# MQ.net
KiCad netlist of a schematic drawn in EAGLE
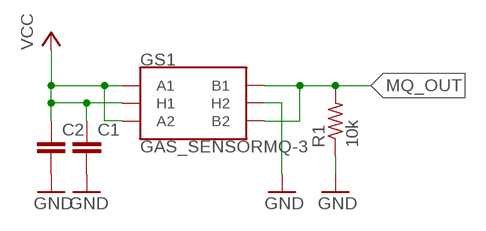
[diagram p0: schematic, sheet 1]

(export (version "E")
  (design (tool "Eeschema 10.0.6"))
  (components
    (comp (ref "C1")
      (value "C-EUC0603")
      (footprint "eagle-import:C0603")
      (libsource (lib "eagle-import") (part "C-EUC0603"))
    )
    (comp (ref "C2")
      (value "C-EUC0603")
      (footprint "eagle-import:C0603")
      (libsource (lib "eagle-import") (part "C-EUC0603"))
    )
    (comp (ref "GS1")
      (value "GAS_SENSORMQ-3")
      (footprint "eagle-import:GAS_SENSOR")
      (libsource (lib "eagle-import") (part "GAS_SENSORMQ-3"))
    )
    (comp (ref "R1")
      (value "10k")
      (footprint "eagle-import:R0603")
      (libsource (lib "eagle-import") (part "R-US_R0603"))
    )
  )
  (nets
    (net (code "1") (name "GND") (class "Default")
      (node (ref "C1") (pin "2") (pinfunction "2_2") (pintype "passive"))
      (node (ref "C2") (pin "2") (pinfunction "2_2") (pintype "passive"))
      (node (ref "GS1") (pin "HB") (pinfunction "H2_HB") (pintype "bidirectional"))
      (node (ref "R1") (pin "1") (pinfunction "1_1") (pintype "passive"))
    )
    (net (code "2") (name "MQ_OUT") (class "Default")
      (node (ref "GS1") (pin "B1") (pinfunction "B1_B1") (pintype "bidirectional"))
      (node (ref "GS1") (pin "B2") (pinfunction "B2_B2") (pintype "bidirectional"))
      (node (ref "R1") (pin "2") (pinfunction "2_2") (pintype "passive"))
    )
    (net (code "3") (name "VCC") (class "Default")
      (node (ref "C1") (pin "1") (pinfunction "1_1") (pintype "passive"))
      (node (ref "C2") (pin "1") (pinfunction "1_1") (pintype "passive"))
      (node (ref "GS1") (pin "A1") (pinfunction "A1_A1") (pintype "bidirectional"))
      (node (ref "GS1") (pin "A2") (pinfunction "A2_A2") (pintype "bidirectional"))
      (node (ref "GS1") (pin "HA") (pinfunction "H1_HA") (pintype "bidirectional"))
    )
  )
)
